# Conn_B.net
KiCad netlist of a schematic drawn in Altium Designer
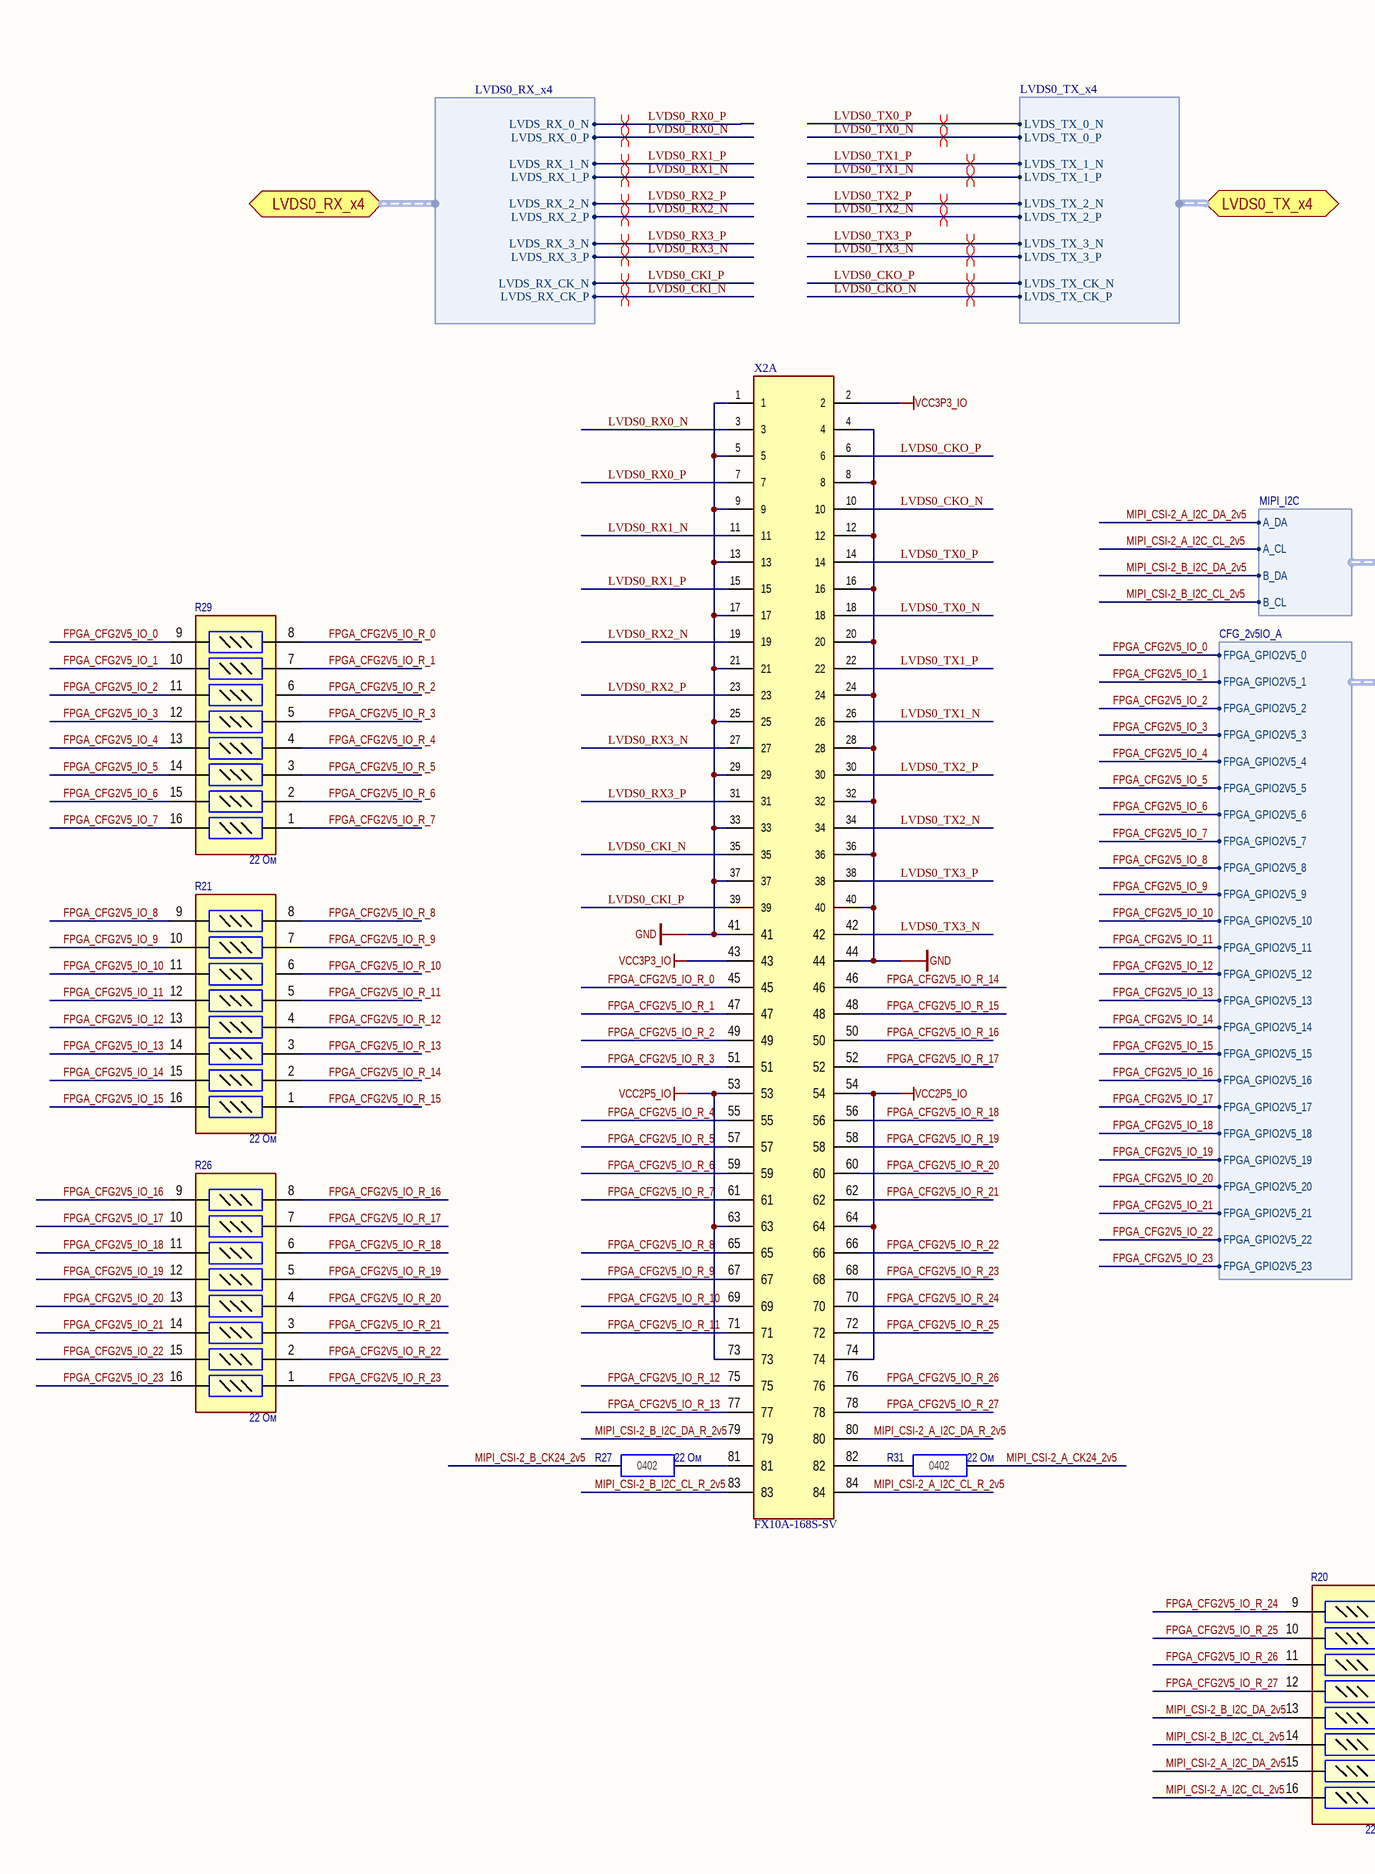
[diagram p0: Conn_B.SchDoc, left]
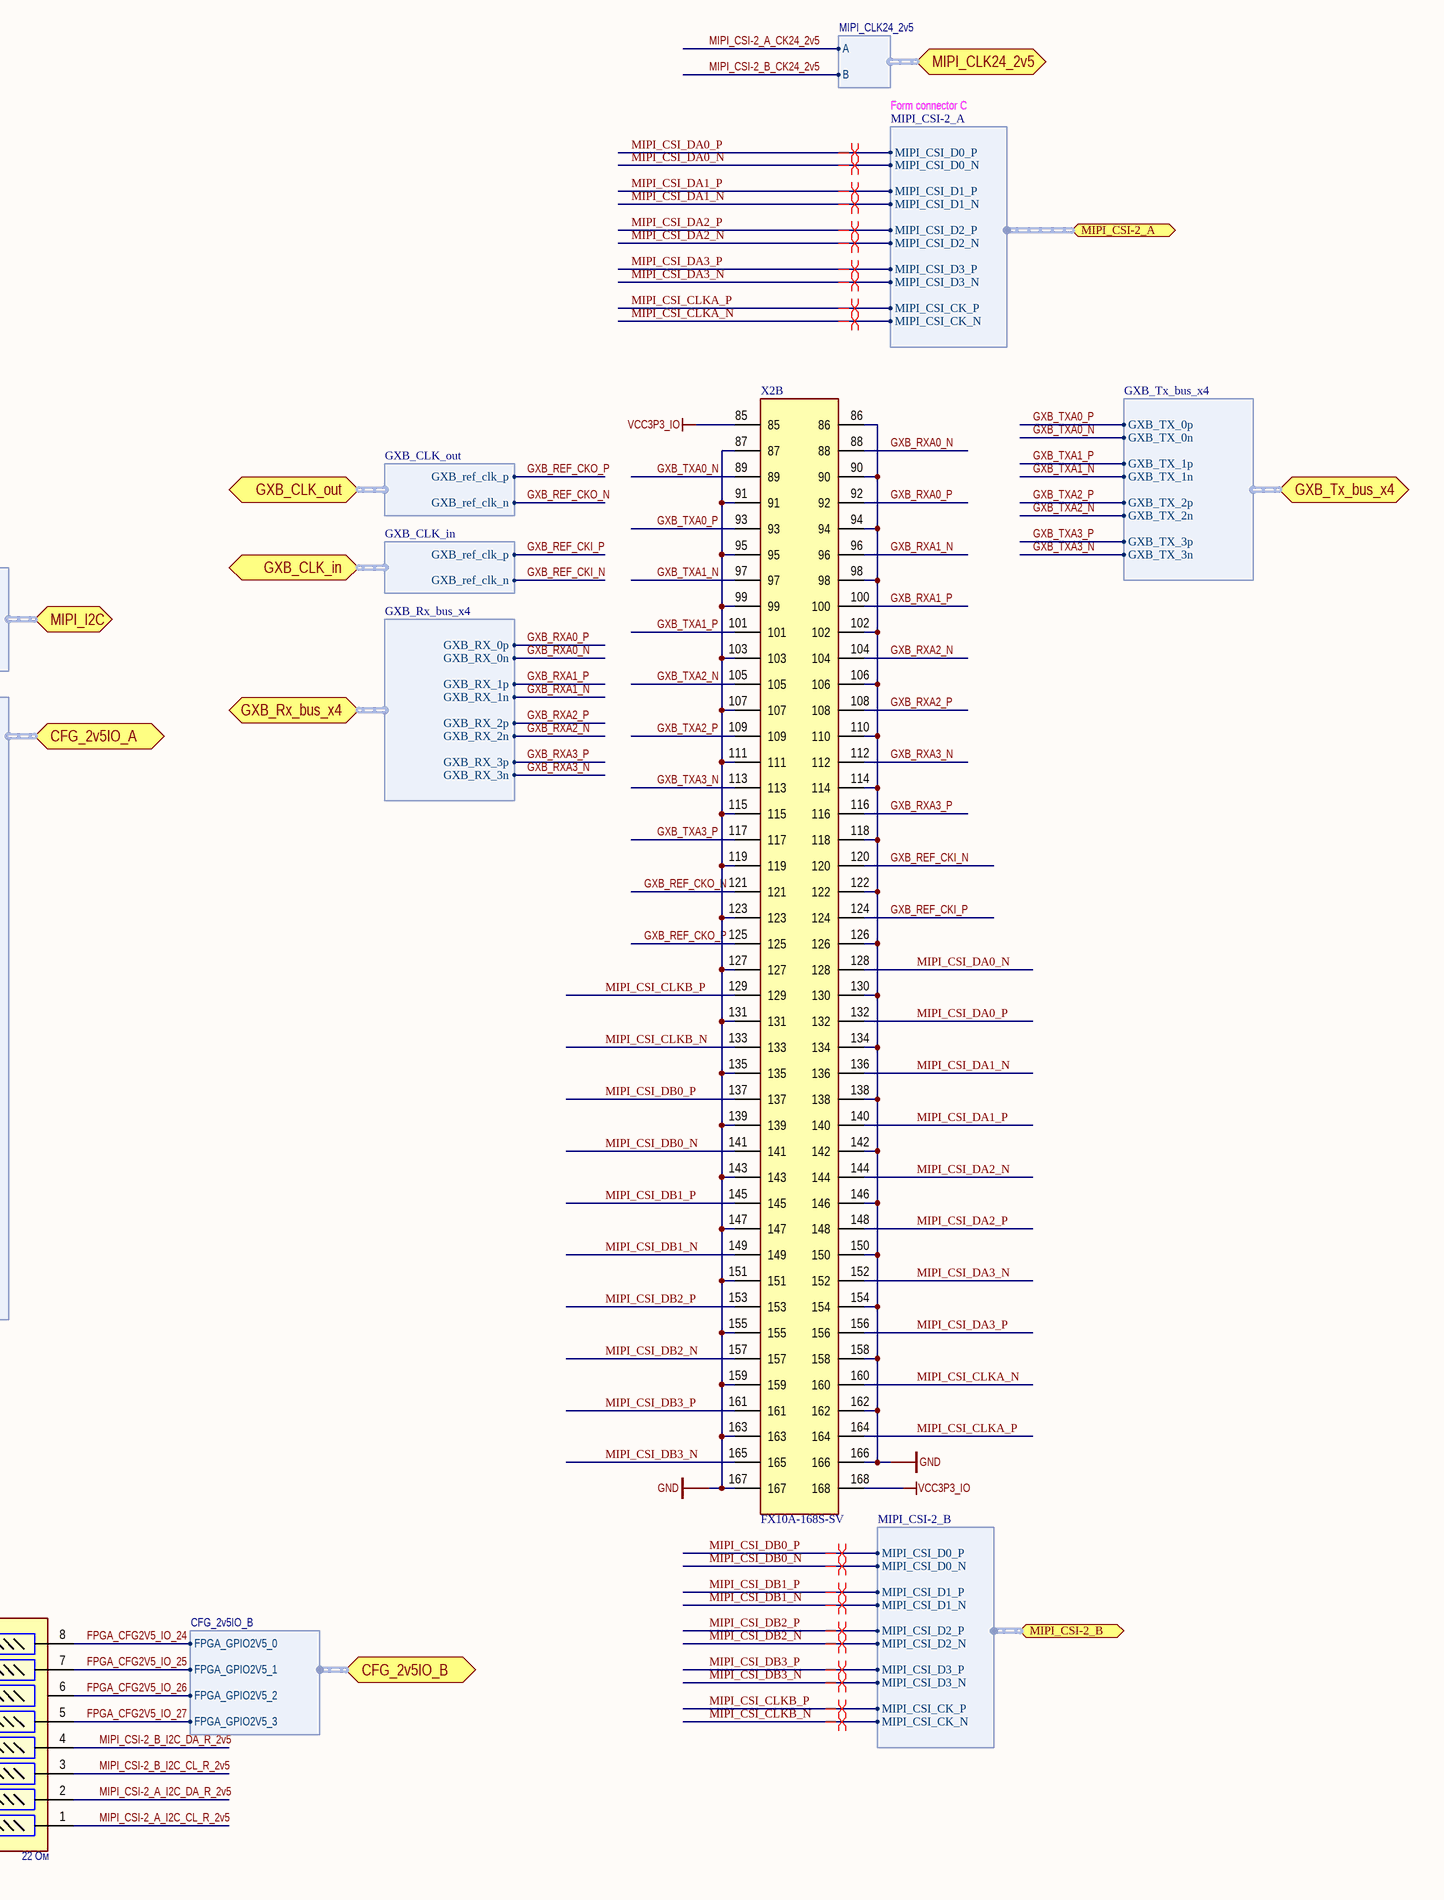
[diagram p1: Conn_B.SchDoc, right]

(export (version "E")
  (design (tool "Eeschema 10.0.6"))
  (components
    (comp (ref "R20")
      (value "22 Ом")
      (footprint "CAT16-J8")
      (description "Набор чип резисторов")
      (fields (field (name "Comment") "YC248-JR-07-22 Ом"))
      (libsource (lib "SD_IC") (part "YC248-JR-07-#"))
    )
    (comp (ref "R21")
      (value "22 Ом")
      (footprint "CAT16-J8")
      (description "Набор чип резисторов")
      (fields (field (name "Comment") "YC248-JR-07-22 Ом"))
      (libsource (lib "SD_IC") (part "YC248-JR-07-#"))
    )
    (comp (ref "R26")
      (value "22 Ом")
      (footprint "CAT16-J8")
      (description "Набор чип резисторов")
      (fields (field (name "Comment") "YC248-JR-07-22 Ом"))
      (libsource (lib "SD_IC") (part "YC248-JR-07-#"))
    )
    (comp (ref "R27")
      (value "22 Ом")
      (footprint "CR0402(1005)")
      (description "Чип резистор")
      (fields (field (name "TOLERANCE") "5%") (field (name "Comment") "CR0402-22 Ом-±5%"))
      (libsource (lib "Чип резисторы") (part "CR0402-#-±5%"))
    )
    (comp (ref "R29")
      (value "22 Ом")
      (footprint "CAT16-J8")
      (description "Набор чип резисторов")
      (fields (field (name "Comment") "YC248-JR-07-22 Ом"))
      (libsource (lib "SD_IC") (part "YC248-JR-07-#"))
    )
    (comp (ref "R31")
      (value "22 Ом")
      (footprint "CR0402(1005)")
      (description "Чип резистор")
      (fields (field (name "TOLERANCE") "5%") (field (name "Comment") "CR0402-22 Ом-±5%"))
      (libsource (lib "Чип резисторы") (part "CR0402-#-±5%"))
    )
    (comp (ref "X2")
      (value "FX10A-168S-SV")
      (footprint "FX10A-168S-SV")
      (libsource (lib "SD_IC") (part "FX10A-168S-SV"))
    )
  )
  (nets
    (net (code "13") (name "/FPGA_CFG2V5_IO_0") (class "Default")
      (node (ref "R29") (pin "9") (pintype "passive"))
    )
    (net (code "14") (name "/FPGA_CFG2V5_IO_1") (class "Default")
      (node (ref "R29") (pin "10") (pintype "passive"))
    )
    (net (code "15") (name "/FPGA_CFG2V5_IO_2") (class "Default")
      (node (ref "R29") (pin "11") (pintype "passive"))
    )
    (net (code "16") (name "/FPGA_CFG2V5_IO_3") (class "Default")
      (node (ref "R29") (pin "12") (pintype "passive"))
    )
    (net (code "17") (name "/FPGA_CFG2V5_IO_4") (class "Default")
      (node (ref "R29") (pin "13") (pintype "passive"))
    )
    (net (code "18") (name "/FPGA_CFG2V5_IO_5") (class "Default")
      (node (ref "R29") (pin "14") (pintype "passive"))
    )
    (net (code "19") (name "/FPGA_CFG2V5_IO_6") (class "Default")
      (node (ref "R29") (pin "15") (pintype "passive"))
    )
    (net (code "20") (name "/FPGA_CFG2V5_IO_7") (class "Default")
      (node (ref "R29") (pin "16") (pintype "passive"))
    )
    (net (code "21") (name "/FPGA_CFG2V5_IO_8") (class "Default")
      (node (ref "R21") (pin "9") (pintype "passive"))
    )
    (net (code "22") (name "/FPGA_CFG2V5_IO_9") (class "Default")
      (node (ref "R21") (pin "10") (pintype "passive"))
    )
    (net (code "23") (name "/FPGA_CFG2V5_IO_10") (class "Default")
      (node (ref "R21") (pin "11") (pintype "passive"))
    )
    (net (code "24") (name "/FPGA_CFG2V5_IO_11") (class "Default")
      (node (ref "R21") (pin "12") (pintype "passive"))
    )
    (net (code "25") (name "/FPGA_CFG2V5_IO_12") (class "Default")
      (node (ref "R21") (pin "13") (pintype "passive"))
    )
    (net (code "26") (name "/FPGA_CFG2V5_IO_13") (class "Default")
      (node (ref "R21") (pin "14") (pintype "passive"))
    )
    (net (code "27") (name "/FPGA_CFG2V5_IO_14") (class "Default")
      (node (ref "R21") (pin "15") (pintype "passive"))
    )
    (net (code "28") (name "/FPGA_CFG2V5_IO_15") (class "Default")
      (node (ref "R21") (pin "16") (pintype "passive"))
    )
    (net (code "29") (name "/FPGA_CFG2V5_IO_16") (class "Default")
      (node (ref "R26") (pin "9") (pintype "passive"))
    )
    (net (code "30") (name "/FPGA_CFG2V5_IO_17") (class "Default")
      (node (ref "R26") (pin "10") (pintype "passive"))
    )
    (net (code "31") (name "/FPGA_CFG2V5_IO_18") (class "Default")
      (node (ref "R26") (pin "11") (pintype "passive"))
    )
    (net (code "32") (name "/FPGA_CFG2V5_IO_19") (class "Default")
      (node (ref "R26") (pin "12") (pintype "passive"))
    )
    (net (code "33") (name "/FPGA_CFG2V5_IO_20") (class "Default")
      (node (ref "R26") (pin "13") (pintype "passive"))
    )
    (net (code "34") (name "/FPGA_CFG2V5_IO_21") (class "Default")
      (node (ref "R26") (pin "14") (pintype "passive"))
    )
    (net (code "35") (name "/FPGA_CFG2V5_IO_22") (class "Default")
      (node (ref "R26") (pin "15") (pintype "passive"))
    )
    (net (code "36") (name "/FPGA_CFG2V5_IO_23") (class "Default")
      (node (ref "R26") (pin "16") (pintype "passive"))
    )
    (net (code "37") (name "/FPGA_CFG2V5_IO_24") (class "Default")
      (node (ref "R20") (pin "8") (pintype "passive"))
    )
    (net (code "38") (name "/FPGA_CFG2V5_IO_25") (class "Default")
      (node (ref "R20") (pin "7") (pintype "passive"))
    )
    (net (code "39") (name "/FPGA_CFG2V5_IO_26") (class "Default")
      (node (ref "R20") (pin "6") (pintype "passive"))
    )
    (net (code "40") (name "/FPGA_CFG2V5_IO_27") (class "Default")
      (node (ref "R20") (pin "5") (pintype "passive"))
    )
    (net (code "41") (name "/FPGA_CFG2V5_IO_R_0") (class "Default")
      (node (ref "R29") (pin "8") (pintype "passive"))
      (node (ref "X2") (pin "45") (pinfunction "45_45") (pintype "passive"))
    )
    (net (code "42") (name "/FPGA_CFG2V5_IO_R_1") (class "Default")
      (node (ref "R29") (pin "7") (pintype "passive"))
      (node (ref "X2") (pin "47") (pinfunction "47_47") (pintype "passive"))
    )
    (net (code "43") (name "/FPGA_CFG2V5_IO_R_2") (class "Default")
      (node (ref "R29") (pin "6") (pintype "passive"))
      (node (ref "X2") (pin "49") (pinfunction "49_49") (pintype "passive"))
    )
    (net (code "44") (name "/FPGA_CFG2V5_IO_R_3") (class "Default")
      (node (ref "R29") (pin "5") (pintype "passive"))
      (node (ref "X2") (pin "51") (pinfunction "51_51") (pintype "passive"))
    )
    (net (code "45") (name "/FPGA_CFG2V5_IO_R_4") (class "Default")
      (node (ref "R29") (pin "4") (pintype "passive"))
      (node (ref "X2") (pin "55") (pinfunction "55_55") (pintype "passive"))
    )
    (net (code "46") (name "/FPGA_CFG2V5_IO_R_5") (class "Default")
      (node (ref "R29") (pin "3") (pintype "passive"))
      (node (ref "X2") (pin "57") (pinfunction "57_57") (pintype "passive"))
    )
    (net (code "47") (name "/FPGA_CFG2V5_IO_R_6") (class "Default")
      (node (ref "R29") (pin "2") (pintype "passive"))
      (node (ref "X2") (pin "59") (pinfunction "59_59") (pintype "passive"))
    )
    (net (code "48") (name "/FPGA_CFG2V5_IO_R_7") (class "Default")
      (node (ref "R29") (pin "1") (pintype "passive"))
      (node (ref "X2") (pin "61") (pinfunction "61_61") (pintype "passive"))
    )
    (net (code "49") (name "/FPGA_CFG2V5_IO_R_8") (class "Default")
      (node (ref "R21") (pin "8") (pintype "passive"))
      (node (ref "X2") (pin "65") (pinfunction "65_65") (pintype "passive"))
    )
    (net (code "50") (name "/FPGA_CFG2V5_IO_R_9") (class "Default")
      (node (ref "R21") (pin "7") (pintype "passive"))
      (node (ref "X2") (pin "67") (pinfunction "67_67") (pintype "passive"))
    )
    (net (code "51") (name "/FPGA_CFG2V5_IO_R_10") (class "Default")
      (node (ref "R21") (pin "6") (pintype "passive"))
      (node (ref "X2") (pin "69") (pinfunction "69_69") (pintype "passive"))
    )
    (net (code "52") (name "/FPGA_CFG2V5_IO_R_11") (class "Default")
      (node (ref "R21") (pin "5") (pintype "passive"))
      (node (ref "X2") (pin "71") (pinfunction "71_71") (pintype "passive"))
    )
    (net (code "53") (name "/FPGA_CFG2V5_IO_R_12") (class "Default")
      (node (ref "R21") (pin "4") (pintype "passive"))
      (node (ref "X2") (pin "75") (pinfunction "75_75") (pintype "passive"))
    )
    (net (code "54") (name "/FPGA_CFG2V5_IO_R_13") (class "Default")
      (node (ref "R21") (pin "3") (pintype "passive"))
      (node (ref "X2") (pin "77") (pinfunction "77_77") (pintype "passive"))
    )
    (net (code "55") (name "/FPGA_CFG2V5_IO_R_14") (class "Default")
      (node (ref "R21") (pin "2") (pintype "passive"))
      (node (ref "X2") (pin "46") (pinfunction "46_46") (pintype "passive"))
    )
    (net (code "56") (name "/FPGA_CFG2V5_IO_R_15") (class "Default")
      (node (ref "R21") (pin "1") (pintype "passive"))
      (node (ref "X2") (pin "48") (pinfunction "48_48") (pintype "passive"))
    )
    (net (code "57") (name "/FPGA_CFG2V5_IO_R_16") (class "Default")
      (node (ref "R26") (pin "8") (pintype "passive"))
      (node (ref "X2") (pin "50") (pinfunction "50_50") (pintype "passive"))
    )
    (net (code "58") (name "/FPGA_CFG2V5_IO_R_17") (class "Default")
      (node (ref "R26") (pin "7") (pintype "passive"))
      (node (ref "X2") (pin "52") (pinfunction "52_52") (pintype "passive"))
    )
    (net (code "59") (name "/FPGA_CFG2V5_IO_R_18") (class "Default")
      (node (ref "R26") (pin "6") (pintype "passive"))
      (node (ref "X2") (pin "56") (pinfunction "56_56") (pintype "passive"))
    )
    (net (code "60") (name "/FPGA_CFG2V5_IO_R_19") (class "Default")
      (node (ref "R26") (pin "5") (pintype "passive"))
      (node (ref "X2") (pin "58") (pinfunction "58_58") (pintype "passive"))
    )
    (net (code "61") (name "/FPGA_CFG2V5_IO_R_20") (class "Default")
      (node (ref "R26") (pin "4") (pintype "passive"))
      (node (ref "X2") (pin "60") (pinfunction "60_60") (pintype "passive"))
    )
    (net (code "62") (name "/FPGA_CFG2V5_IO_R_21") (class "Default")
      (node (ref "R26") (pin "3") (pintype "passive"))
      (node (ref "X2") (pin "62") (pinfunction "62_62") (pintype "passive"))
    )
    (net (code "63") (name "/FPGA_CFG2V5_IO_R_22") (class "Default")
      (node (ref "R26") (pin "2") (pintype "passive"))
      (node (ref "X2") (pin "66") (pinfunction "66_66") (pintype "passive"))
    )
    (net (code "64") (name "/FPGA_CFG2V5_IO_R_23") (class "Default")
      (node (ref "R26") (pin "1") (pintype "passive"))
      (node (ref "X2") (pin "68") (pinfunction "68_68") (pintype "passive"))
    )
    (net (code "65") (name "/FPGA_CFG2V5_IO_R_24") (class "Default")
      (node (ref "R20") (pin "9") (pintype "passive"))
      (node (ref "X2") (pin "70") (pinfunction "70_70") (pintype "passive"))
    )
    (net (code "66") (name "/FPGA_CFG2V5_IO_R_25") (class "Default")
      (node (ref "R20") (pin "10") (pintype "passive"))
      (node (ref "X2") (pin "72") (pinfunction "72_72") (pintype "passive"))
    )
    (net (code "67") (name "/FPGA_CFG2V5_IO_R_26") (class "Default")
      (node (ref "R20") (pin "11") (pintype "passive"))
      (node (ref "X2") (pin "76") (pinfunction "76_76") (pintype "passive"))
    )
    (net (code "68") (name "/FPGA_CFG2V5_IO_R_27") (class "Default")
      (node (ref "R20") (pin "12") (pintype "passive"))
      (node (ref "X2") (pin "78") (pinfunction "78_78") (pintype "passive"))
    )
    (net (code "69") (name "/GXB_REF_CKI_N") (class "Default")
      (node (ref "X2") (pin "120") (pinfunction "120_120") (pintype "passive"))
    )
    (net (code "70") (name "/GXB_REF_CKI_P") (class "Default")
      (node (ref "X2") (pin "124") (pinfunction "124_124") (pintype "passive"))
    )
    (net (code "71") (name "/GXB_REF_CKO_N") (class "Default")
      (node (ref "X2") (pin "121") (pinfunction "121_121") (pintype "passive"))
    )
    (net (code "72") (name "/GXB_REF_CKO_P") (class "Default")
      (node (ref "X2") (pin "125") (pinfunction "125_125") (pintype "passive"))
    )
    (net (code "73") (name "/GXB_RXA0_N") (class "Default")
      (node (ref "X2") (pin "88") (pinfunction "88_88") (pintype "passive"))
    )
    (net (code "74") (name "/GXB_RXA0_P") (class "Default")
      (node (ref "X2") (pin "92") (pinfunction "92_92") (pintype "passive"))
    )
    (net (code "75") (name "/GXB_RXA1_N") (class "Default")
      (node (ref "X2") (pin "96") (pinfunction "96_96") (pintype "passive"))
    )
    (net (code "76") (name "/GXB_RXA1_P") (class "Default")
      (node (ref "X2") (pin "100") (pinfunction "100_100") (pintype "passive"))
    )
    (net (code "77") (name "/GXB_RXA2_N") (class "Default")
      (node (ref "X2") (pin "104") (pinfunction "104_104") (pintype "passive"))
    )
    (net (code "78") (name "/GXB_RXA2_P") (class "Default")
      (node (ref "X2") (pin "108") (pinfunction "108_108") (pintype "passive"))
    )
    (net (code "79") (name "/GXB_RXA3_N") (class "Default")
      (node (ref "X2") (pin "112") (pinfunction "112_112") (pintype "passive"))
    )
    (net (code "80") (name "/GXB_RXA3_P") (class "Default")
      (node (ref "X2") (pin "116") (pinfunction "116_116") (pintype "passive"))
    )
    (net (code "81") (name "/GXB_TXA0_N") (class "Default")
      (node (ref "X2") (pin "89") (pinfunction "89_89") (pintype "passive"))
    )
    (net (code "82") (name "/GXB_TXA0_P") (class "Default")
      (node (ref "X2") (pin "93") (pinfunction "93_93") (pintype "passive"))
    )
    (net (code "83") (name "/GXB_TXA1_N") (class "Default")
      (node (ref "X2") (pin "97") (pinfunction "97_97") (pintype "passive"))
    )
    (net (code "84") (name "/GXB_TXA1_P") (class "Default")
      (node (ref "X2") (pin "101") (pinfunction "101_101") (pintype "passive"))
    )
    (net (code "85") (name "/GXB_TXA2_N") (class "Default")
      (node (ref "X2") (pin "105") (pinfunction "105_105") (pintype "passive"))
    )
    (net (code "86") (name "/GXB_TXA2_P") (class "Default")
      (node (ref "X2") (pin "109") (pinfunction "109_109") (pintype "passive"))
    )
    (net (code "87") (name "/GXB_TXA3_N") (class "Default")
      (node (ref "X2") (pin "113") (pinfunction "113_113") (pintype "passive"))
    )
    (net (code "88") (name "/GXB_TXA3_P") (class "Default")
      (node (ref "X2") (pin "117") (pinfunction "117_117") (pintype "passive"))
    )
    (net (code "89") (name "/LVDS0_CKI_N") (class "Default")
      (node (ref "X2") (pin "35") (pinfunction "35_35") (pintype "passive"))
    )
    (net (code "90") (name "/LVDS0_CKI_P") (class "Default")
      (node (ref "X2") (pin "39") (pinfunction "39_39") (pintype "passive"))
    )
    (net (code "91") (name "/LVDS0_CKO_N") (class "Default")
      (node (ref "X2") (pin "10") (pinfunction "10_10") (pintype "passive"))
    )
    (net (code "92") (name "/LVDS0_CKO_P") (class "Default")
      (node (ref "X2") (pin "6") (pinfunction "6_6") (pintype "passive"))
    )
    (net (code "93") (name "/LVDS0_RX0_N") (class "Default")
      (node (ref "X2") (pin "3") (pinfunction "3_3") (pintype "passive"))
    )
    (net (code "94") (name "/LVDS0_RX0_P") (class "Default")
      (node (ref "X2") (pin "7") (pinfunction "7_7") (pintype "passive"))
    )
    (net (code "95") (name "/LVDS0_RX1_N") (class "Default")
      (node (ref "X2") (pin "11") (pinfunction "11_11") (pintype "passive"))
    )
    (net (code "96") (name "/LVDS0_RX1_P") (class "Default")
      (node (ref "X2") (pin "15") (pinfunction "15_15") (pintype "passive"))
    )
    (net (code "97") (name "/LVDS0_RX2_N") (class "Default")
      (node (ref "X2") (pin "19") (pinfunction "19_19") (pintype "passive"))
    )
    (net (code "98") (name "/LVDS0_RX2_P") (class "Default")
      (node (ref "X2") (pin "23") (pinfunction "23_23") (pintype "passive"))
    )
    (net (code "99") (name "/LVDS0_RX3_N") (class "Default")
      (node (ref "X2") (pin "27") (pinfunction "27_27") (pintype "passive"))
    )
    (net (code "100") (name "/LVDS0_RX3_P") (class "Default")
      (node (ref "X2") (pin "31") (pinfunction "31_31") (pintype "passive"))
    )
    (net (code "101") (name "/LVDS0_TX0_N") (class "Default")
      (node (ref "X2") (pin "18") (pinfunction "18_18") (pintype "passive"))
    )
    (net (code "102") (name "/LVDS0_TX0_P") (class "Default")
      (node (ref "X2") (pin "14") (pinfunction "14_14") (pintype "passive"))
    )
    (net (code "103") (name "/LVDS0_TX1_N") (class "Default")
      (node (ref "X2") (pin "26") (pinfunction "26_26") (pintype "passive"))
    )
    (net (code "104") (name "/LVDS0_TX1_P") (class "Default")
      (node (ref "X2") (pin "22") (pinfunction "22_22") (pintype "passive"))
    )
    (net (code "105") (name "/LVDS0_TX2_N") (class "Default")
      (node (ref "X2") (pin "34") (pinfunction "34_34") (pintype "passive"))
    )
    (net (code "106") (name "/LVDS0_TX2_P") (class "Default")
      (node (ref "X2") (pin "30") (pinfunction "30_30") (pintype "passive"))
    )
    (net (code "107") (name "/LVDS0_TX3_N") (class "Default")
      (node (ref "X2") (pin "42") (pinfunction "42_42") (pintype "passive"))
    )
    (net (code "108") (name "/LVDS0_TX3_P") (class "Default")
      (node (ref "X2") (pin "38") (pinfunction "38_38") (pintype "passive"))
    )
    (net (code "109") (name "/MIPI_CSI-2_A_CK24_2v5") (class "Default")
      (node (ref "R31") (pin "2") (pinfunction "-_2") (pintype "passive"))
    )
    (net (code "110") (name "/MIPI_CSI-2_A_I2C_CL_2v5") (class "Default")
      (node (ref "R20") (pin "16") (pintype "passive"))
    )
    (net (code "111") (name "/MIPI_CSI-2_A_I2C_CL_R_2v5") (class "Default")
      (node (ref "R20") (pin "1") (pintype "passive"))
      (node (ref "X2") (pin "84") (pinfunction "84_84") (pintype "passive"))
    )
    (net (code "112") (name "/MIPI_CSI-2_A_I2C_DA_2v5") (class "Default")
      (node (ref "R20") (pin "15") (pintype "passive"))
    )
    (net (code "113") (name "/MIPI_CSI-2_A_I2C_DA_R_2v5") (class "Default")
      (node (ref "R20") (pin "2") (pintype "passive"))
      (node (ref "X2") (pin "80") (pinfunction "80_80") (pintype "passive"))
    )
    (net (code "114") (name "/MIPI_CSI-2_B_CK24_2v5") (class "Default")
      (node (ref "R27") (pin "1") (pinfunction "+_1") (pintype "passive"))
    )
    (net (code "115") (name "/MIPI_CSI-2_B_I2C_CL_2v5") (class "Default")
      (node (ref "R20") (pin "14") (pintype "passive"))
    )
    (net (code "116") (name "/MIPI_CSI-2_B_I2C_CL_R_2v5") (class "Default")
      (node (ref "R20") (pin "3") (pintype "passive"))
      (node (ref "X2") (pin "83") (pinfunction "83_83") (pintype "passive"))
    )
    (net (code "117") (name "/MIPI_CSI-2_B_I2C_DA_2v5") (class "Default")
      (node (ref "R20") (pin "13") (pintype "passive"))
    )
    (net (code "118") (name "/MIPI_CSI-2_B_I2C_DA_R_2v5") (class "Default")
      (node (ref "R20") (pin "4") (pintype "passive"))
      (node (ref "X2") (pin "79") (pinfunction "79_79") (pintype "passive"))
    )
    (net (code "119") (name "/MIPI_CSI_CLKA_N") (class "Default")
      (node (ref "X2") (pin "160") (pinfunction "160_160") (pintype "passive"))
    )
    (net (code "120") (name "/MIPI_CSI_CLKA_P") (class "Default")
      (node (ref "X2") (pin "164") (pinfunction "164_164") (pintype "passive"))
    )
    (net (code "121") (name "/MIPI_CSI_CLKB_N") (class "Default")
      (node (ref "X2") (pin "133") (pinfunction "133_133") (pintype "passive"))
    )
    (net (code "122") (name "/MIPI_CSI_CLKB_P") (class "Default")
      (node (ref "X2") (pin "129") (pinfunction "129_129") (pintype "passive"))
    )
    (net (code "123") (name "/MIPI_CSI_DA0_N") (class "Default")
      (node (ref "X2") (pin "128") (pinfunction "128_128") (pintype "passive"))
    )
    (net (code "124") (name "/MIPI_CSI_DA0_P") (class "Default")
      (node (ref "X2") (pin "132") (pinfunction "132_132") (pintype "passive"))
    )
    (net (code "125") (name "/MIPI_CSI_DA1_N") (class "Default")
      (node (ref "X2") (pin "136") (pinfunction "136_136") (pintype "passive"))
    )
    (net (code "126") (name "/MIPI_CSI_DA1_P") (class "Default")
      (node (ref "X2") (pin "140") (pinfunction "140_140") (pintype "passive"))
    )
    (net (code "127") (name "/MIPI_CSI_DA2_N") (class "Default")
      (node (ref "X2") (pin "144") (pinfunction "144_144") (pintype "passive"))
    )
    (net (code "128") (name "/MIPI_CSI_DA2_P") (class "Default")
      (node (ref "X2") (pin "148") (pinfunction "148_148") (pintype "passive"))
    )
    (net (code "129") (name "/MIPI_CSI_DA3_N") (class "Default")
      (node (ref "X2") (pin "152") (pinfunction "152_152") (pintype "passive"))
    )
    (net (code "130") (name "/MIPI_CSI_DA3_P") (class "Default")
      (node (ref "X2") (pin "156") (pinfunction "156_156") (pintype "passive"))
    )
    (net (code "131") (name "/MIPI_CSI_DB0_N") (class "Default")
      (node (ref "X2") (pin "141") (pinfunction "141_141") (pintype "passive"))
    )
    (net (code "132") (name "/MIPI_CSI_DB0_P") (class "Default")
      (node (ref "X2") (pin "137") (pinfunction "137_137") (pintype "passive"))
    )
    (net (code "133") (name "/MIPI_CSI_DB1_N") (class "Default")
      (node (ref "X2") (pin "149") (pinfunction "149_149") (pintype "passive"))
    )
    (net (code "134") (name "/MIPI_CSI_DB1_P") (class "Default")
      (node (ref "X2") (pin "145") (pinfunction "145_145") (pintype "passive"))
    )
    (net (code "135") (name "/MIPI_CSI_DB2_N") (class "Default")
      (node (ref "X2") (pin "157") (pinfunction "157_157") (pintype "passive"))
    )
    (net (code "136") (name "/MIPI_CSI_DB2_P") (class "Default")
      (node (ref "X2") (pin "153") (pinfunction "153_153") (pintype "passive"))
    )
    (net (code "137") (name "/MIPI_CSI_DB3_N") (class "Default")
      (node (ref "X2") (pin "165") (pinfunction "165_165") (pintype "passive"))
    )
    (net (code "138") (name "/MIPI_CSI_DB3_P") (class "Default")
      (node (ref "X2") (pin "161") (pinfunction "161_161") (pintype "passive"))
    )
    (net (code "151") (name "GND") (class "Default")
      (node (ref "X2") (pin "1") (pinfunction "1_1") (pintype "passive"))
      (node (ref "X2") (pin "102") (pinfunction "102_102") (pintype "passive"))
      (node (ref "X2") (pin "103") (pinfunction "103_103") (pintype "passive"))
      (node (ref "X2") (pin "106") (pinfunction "106_106") (pintype "passive"))
      (node (ref "X2") (pin "107") (pinfunction "107_107") (pintype "passive"))
      (node (ref "X2") (pin "110") (pinfunction "110_110") (pintype "passive"))
      (node (ref "X2") (pin "111") (pinfunction "111_111") (pintype "passive"))
      (node (ref "X2") (pin "114") (pinfunction "114_114") (pintype "passive"))
      (node (ref "X2") (pin "115") (pinfunction "115_115") (pintype "passive"))
      (node (ref "X2") (pin "118") (pinfunction "118_118") (pintype "passive"))
      (node (ref "X2") (pin "119") (pinfunction "119_119") (pintype "passive"))
      (node (ref "X2") (pin "12") (pinfunction "12_12") (pintype "passive"))
      (node (ref "X2") (pin "122") (pinfunction "122_122") (pintype "passive"))
      (node (ref "X2") (pin "123") (pinfunction "123_123") (pintype "passive"))
      (node (ref "X2") (pin "126") (pinfunction "126_126") (pintype "passive"))
      (node (ref "X2") (pin "127") (pinfunction "127_127") (pintype "passive"))
      (node (ref "X2") (pin "13") (pinfunction "13_13") (pintype "passive"))
      (node (ref "X2") (pin "130") (pinfunction "130_130") (pintype "passive"))
      (node (ref "X2") (pin "131") (pinfunction "131_131") (pintype "passive"))
      (node (ref "X2") (pin "134") (pinfunction "134_134") (pintype "passive"))
      (node (ref "X2") (pin "135") (pinfunction "135_135") (pintype "passive"))
      (node (ref "X2") (pin "138") (pinfunction "138_138") (pintype "passive"))
      (node (ref "X2") (pin "139") (pinfunction "139_139") (pintype "passive"))
      (node (ref "X2") (pin "142") (pinfunction "142_142") (pintype "passive"))
      (node (ref "X2") (pin "143") (pinfunction "143_143") (pintype "passive"))
      (node (ref "X2") (pin "146") (pinfunction "146_146") (pintype "passive"))
      (node (ref "X2") (pin "147") (pinfunction "147_147") (pintype "passive"))
      (node (ref "X2") (pin "150") (pinfunction "150_150") (pintype "passive"))
      (node (ref "X2") (pin "151") (pinfunction "151_151") (pintype "passive"))
      (node (ref "X2") (pin "154") (pinfunction "154_154") (pintype "passive"))
      (node (ref "X2") (pin "155") (pinfunction "155_155") (pintype "passive"))
      (node (ref "X2") (pin "158") (pinfunction "158_158") (pintype "passive"))
      (node (ref "X2") (pin "159") (pinfunction "159_159") (pintype "passive"))
      (node (ref "X2") (pin "16") (pinfunction "16_16") (pintype "passive"))
      (node (ref "X2") (pin "162") (pinfunction "162_162") (pintype "passive"))
      (node (ref "X2") (pin "163") (pinfunction "163_163") (pintype "passive"))
      (node (ref "X2") (pin "166") (pinfunction "166_166") (pintype "passive"))
      (node (ref "X2") (pin "167") (pinfunction "167_167") (pintype "passive"))
      (node (ref "X2") (pin "17") (pinfunction "17_17") (pintype "passive"))
      (node (ref "X2") (pin "20") (pinfunction "20_20") (pintype "passive"))
      (node (ref "X2") (pin "21") (pinfunction "21_21") (pintype "passive"))
      (node (ref "X2") (pin "24") (pinfunction "24_24") (pintype "passive"))
      (node (ref "X2") (pin "25") (pinfunction "25_25") (pintype "passive"))
      (node (ref "X2") (pin "28") (pinfunction "28_28") (pintype "passive"))
      (node (ref "X2") (pin "29") (pinfunction "29_29") (pintype "passive"))
      (node (ref "X2") (pin "32") (pinfunction "32_32") (pintype "passive"))
      (node (ref "X2") (pin "33") (pinfunction "33_33") (pintype "passive"))
      (node (ref "X2") (pin "36") (pinfunction "36_36") (pintype "passive"))
      (node (ref "X2") (pin "37") (pinfunction "37_37") (pintype "passive"))
      (node (ref "X2") (pin "4") (pinfunction "4_4") (pintype "passive"))
      (node (ref "X2") (pin "40") (pinfunction "40_40") (pintype "passive"))
      (node (ref "X2") (pin "41") (pinfunction "41_41") (pintype "passive"))
      (node (ref "X2") (pin "44") (pinfunction "44_44") (pintype "passive"))
      (node (ref "X2") (pin "5") (pinfunction "5_5") (pintype "passive"))
      (node (ref "X2") (pin "8") (pinfunction "8_8") (pintype "passive"))
      (node (ref "X2") (pin "86") (pinfunction "86_86") (pintype "passive"))
      (node (ref "X2") (pin "87") (pinfunction "87_87") (pintype "passive"))
      (node (ref "X2") (pin "9") (pinfunction "9_9") (pintype "passive"))
      (node (ref "X2") (pin "90") (pinfunction "90_90") (pintype "passive"))
      (node (ref "X2") (pin "91") (pinfunction "91_91") (pintype "passive"))
      (node (ref "X2") (pin "94") (pinfunction "94_94") (pintype "passive"))
      (node (ref "X2") (pin "95") (pinfunction "95_95") (pintype "passive"))
      (node (ref "X2") (pin "98") (pinfunction "98_98") (pintype "passive"))
      (node (ref "X2") (pin "99") (pinfunction "99_99") (pintype "passive"))
    )
    (net (code "152") (name "Net-(R27--)") (class "Default")
      (node (ref "R27") (pin "2") (pinfunction "-_2") (pintype "passive"))
      (node (ref "X2") (pin "81") (pinfunction "81_81") (pintype "passive"))
    )
    (net (code "153") (name "Net-(R31-+)") (class "Default")
      (node (ref "R31") (pin "1") (pinfunction "+_1") (pintype "passive"))
      (node (ref "X2") (pin "82") (pinfunction "82_82") (pintype "passive"))
    )
    (net (code "154") (name "VCC2P5_IO") (class "Default")
      (node (ref "X2") (pin "53") (pinfunction "53_53") (pintype "passive"))
      (node (ref "X2") (pin "54") (pinfunction "54_54") (pintype "passive"))
      (node (ref "X2") (pin "63") (pinfunction "63_63") (pintype "passive"))
      (node (ref "X2") (pin "64") (pinfunction "64_64") (pintype "passive"))
      (node (ref "X2") (pin "73") (pinfunction "73_73") (pintype "passive"))
      (node (ref "X2") (pin "74") (pinfunction "74_74") (pintype "passive"))
    )
    (net (code "155") (name "VCC3P3_IO") (class "Default")
      (node (ref "X2") (pin "168") (pinfunction "168_168") (pintype "passive"))
      (node (ref "X2") (pin "2") (pinfunction "2_2") (pintype "passive"))
      (node (ref "X2") (pin "43") (pinfunction "43_43") (pintype "passive"))
      (node (ref "X2") (pin "85") (pinfunction "85_85") (pintype "passive"))
    )
  )
)
